# P2_CCD_CAM_BOARD_POWER.net
KiCad netlist of a schematic drawn in Altium Designer
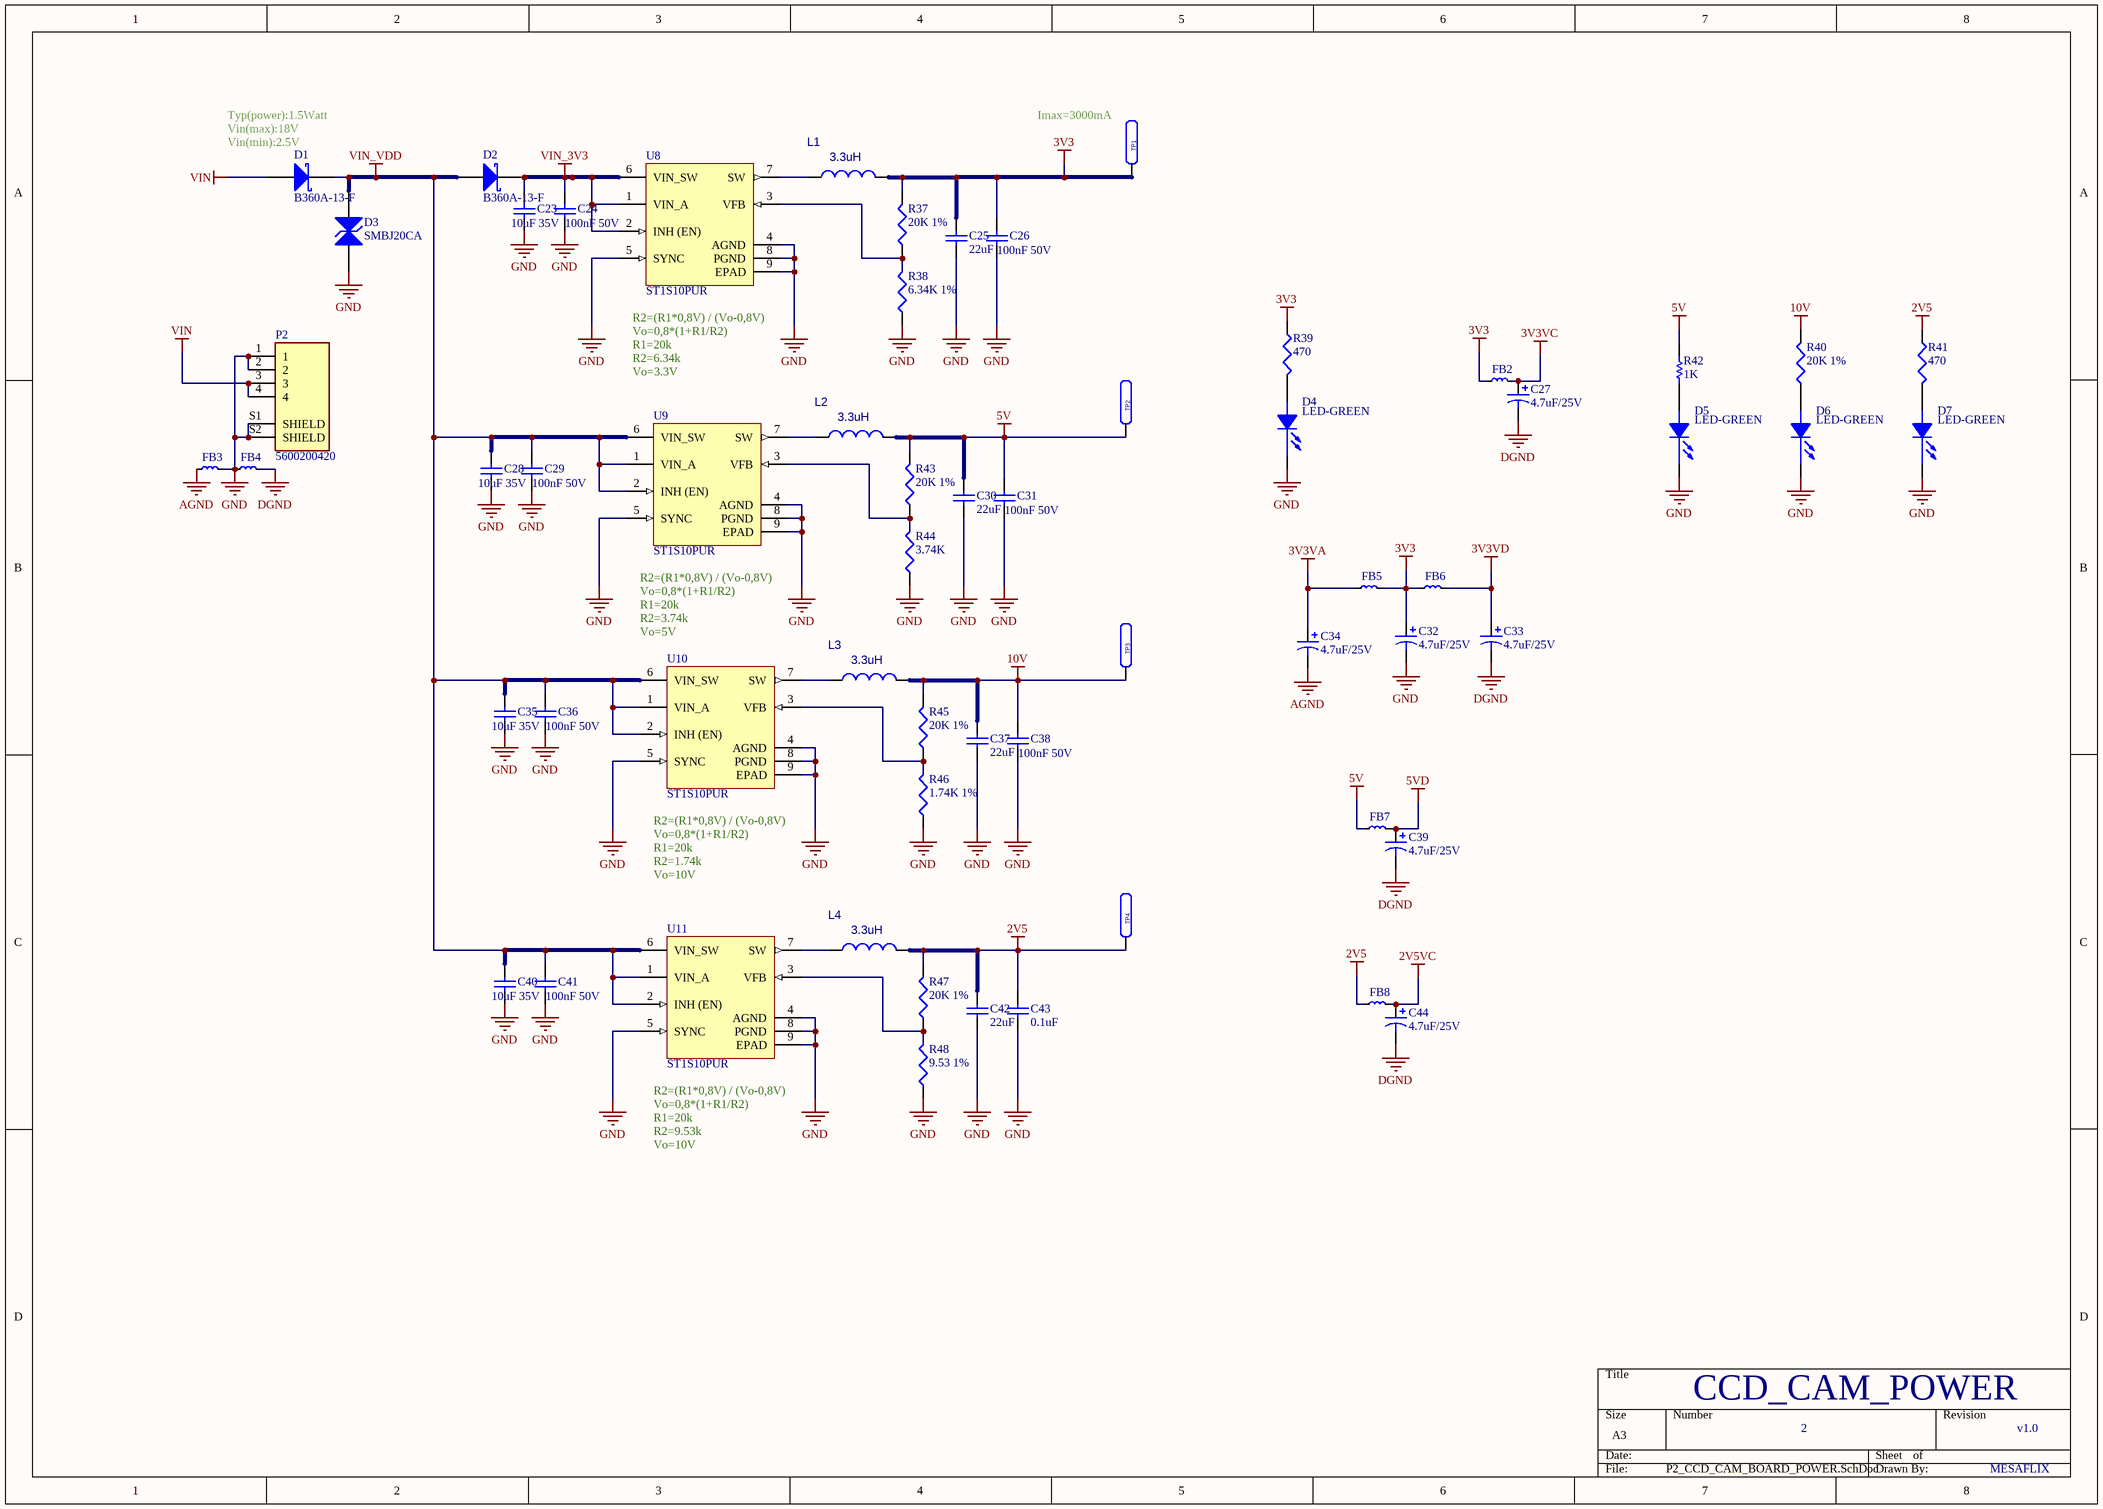
[diagram p0: P2_CCD_CAM_BOARD_POWER.SchDoc]

(export (version "E")
  (design (tool "Eeschema 10.0.6"))
  (components
    (comp (ref "C23")
      (value "10uF 35V")
      (footprint "C 0603(1608)x0.8")
      (description "Cap Ceramic 10uF 35V X5R 20% Pad SMD 0603 85C T/R")
      (fields
        (field (name "MANUFACTURER") "Murata")
        (field (name "MANUFACTURER PART NUMBER") "GRM188R6YA106MA73D")
      )
      (libsource (lib "Miscellaneous Devices") (part "Cap"))
    )
    (comp (ref "C24")
      (value "100nF 50V")
      (footprint "CAP0603")
      (description "CAP CER 0.1UF 50V X7R 0603")
      (libsource (lib "CAP_Library") (part "CAP0603_100nF"))
    )
    (comp (ref "C25")
      (value "22uF")
      (footprint "C 0603(1608)x0.8")
      (description "MURATA - GRM188R60J226MEA0D - CAP, 22µF, 6.3V, 20%, X5R, 0603")
      (fields
        (field (name "MANUFACTURER") "Murata")
        (field (name "MANUFACTURER PART NUMBER") "GRM188R60J226MEA0D")
      )
      (libsource (lib "Miscellaneous Devices") (part "Cap"))
    )
    (comp (ref "C26")
      (value "100nF 50V")
      (footprint "CAP0603")
      (description "CAP CER 0.1UF 50V X7R 0603")
      (libsource (lib "CAP_Library") (part "CAP0603_100nF"))
    )
    (comp (ref "C27")
      (value "4.7uF/25V")
      (footprint "0805 (2012)")
      (fields (field (name "MFR PART #") "GRM219R61E475KA73D"))
      (libsource (lib "CCD_board") (part "Cap Chip Pol"))
    )
    (comp (ref "C28")
      (value "10uF 35V")
      (footprint "C 0603(1608)x0.8")
      (description "Cap Ceramic 10uF 35V X5R 20% Pad SMD 0603 85C T/R")
      (fields
        (field (name "MANUFACTURER") "Murata")
        (field (name "MANUFACTURER PART NUMBER") "GRM188R6YA106MA73D")
      )
      (libsource (lib "Miscellaneous Devices") (part "Cap"))
    )
    (comp (ref "C29")
      (value "100nF 50V")
      (footprint "CAP0603")
      (description "CAP CER 0.1UF 50V X7R 0603")
      (libsource (lib "CAP_Library") (part "CAP0603_100nF"))
    )
    (comp (ref "C30")
      (value "22uF")
      (footprint "C 0603(1608)x0.8")
      (description "MURATA - GRM188R60J226MEA0D - CAP, 22µF, 6.3V, 20%, X5R, 0603")
      (fields
        (field (name "MANUFACTURER") "Murata")
        (field (name "MANUFACTURER PART NUMBER") "GRM188R60J226MEA0D")
      )
      (libsource (lib "Miscellaneous Devices") (part "Cap"))
    )
    (comp (ref "C31")
      (value "100nF 50V")
      (footprint "CAP0603")
      (description "CAP CER 0.1UF 50V X7R 0603")
      (libsource (lib "CAP_Library") (part "CAP0603_100nF"))
    )
    (comp (ref "C32")
      (value "4.7uF/25V")
      (footprint "0805 (2012)")
      (fields (field (name "MFR PART #") "GRM219R61E475KA73D"))
      (libsource (lib "CCD_board") (part "Cap Chip Pol"))
    )
    (comp (ref "C33")
      (value "4.7uF/25V")
      (footprint "0805 (2012)")
      (fields (field (name "MFR PART #") "GRM219R61E475KA73D"))
      (libsource (lib "CCD_board") (part "Cap Chip Pol"))
    )
    (comp (ref "C34")
      (value "4.7uF/25V")
      (footprint "0805 (2012)")
      (fields (field (name "MFR PART #") "GRM219R61E475KA73D"))
      (libsource (lib "CCD_board") (part "Cap Chip Pol"))
    )
    (comp (ref "C35")
      (value "10uF 35V")
      (footprint "C 0603(1608)x0.8")
      (description "Cap Ceramic 10uF 35V X5R 20% Pad SMD 0603 85C T/R")
      (fields
        (field (name "MANUFACTURER") "Murata")
        (field (name "MANUFACTURER PART NUMBER") "GRM188R6YA106MA73D")
      )
      (libsource (lib "Miscellaneous Devices") (part "Cap"))
    )
    (comp (ref "C36")
      (value "100nF 50V")
      (footprint "CAP0603")
      (description "CAP CER 0.1UF 50V X7R 0603")
      (libsource (lib "CAP_Library") (part "CAP0603_100nF"))
    )
    (comp (ref "C37")
      (value "22uF")
      (footprint "C 0603(1608)x0.8")
      (description "MURATA - GRM188R60J226MEA0D - CAP, 22µF, 6.3V, 20%, X5R, 0603")
      (fields
        (field (name "MANUFACTURER") "Murata")
        (field (name "MANUFACTURER PART NUMBER") "GRM188R60J226MEA0D")
      )
      (libsource (lib "Miscellaneous Devices") (part "Cap"))
    )
    (comp (ref "C38")
      (value "100nF 50V")
      (footprint "CAP0603")
      (description "CAP CER 0.1UF 50V X7R 0603")
      (libsource (lib "CAP_Library") (part "CAP0603_100nF"))
    )
    (comp (ref "C39")
      (value "4.7uF/25V")
      (footprint "0805 (2012)")
      (fields (field (name "MFR PART #") "GRM219R61E475KA73D"))
      (libsource (lib "CCD_board") (part "Cap Chip Pol"))
    )
    (comp (ref "C40")
      (value "10uF 35V")
      (footprint "C 0603(1608)x0.8")
      (description "Cap Ceramic 10uF 35V X5R 20% Pad SMD 0603 85C T/R")
      (fields
        (field (name "MANUFACTURER") "Murata")
        (field (name "MANUFACTURER PART NUMBER") "GRM188R6YA106MA73D")
      )
      (libsource (lib "Miscellaneous Devices") (part "Cap"))
    )
    (comp (ref "C41")
      (value "100nF 50V")
      (footprint "CAP0603")
      (description "CAP CER 0.1UF 50V X7R 0603")
      (libsource (lib "CAP_Library") (part "CAP0603_100nF"))
    )
    (comp (ref "C42")
      (value "22uF")
      (footprint "C 0603(1608)x0.8")
      (description "MURATA - GRM188R60J226MEA0D - CAP, 22µF, 6.3V, 20%, X5R, 0603")
      (fields
        (field (name "MANUFACTURER") "Murata")
        (field (name "MANUFACTURER PART NUMBER") "GRM188R60J226MEA0D")
      )
      (libsource (lib "Miscellaneous Devices") (part "Cap"))
    )
    (comp (ref "C43")
      (value "0.1uF")
      (footprint "C 0402(1005)x0.5")
      (description "Capacitor")
      (fields
        (field (name "MANUFACTURER") "Murata")
        (field (name "MANUFACTURER PART NUMBER") "GRM155R71C104KA88D")
      )
      (libsource (lib "Miscellaneous Devices") (part "Cap"))
    )
    (comp (ref "C44")
      (value "4.7uF/25V")
      (footprint "0805 (2012)")
      (fields (field (name "MFR PART #") "GRM219R61E475KA73D"))
      (libsource (lib "CCD_board") (part "Cap Chip Pol"))
    )
    (comp (ref "D1")
      (value "B360A-13-F")
      (footprint "DIOD-B360A_V")
      (description "Schottky Barrier Rectifier, 3 A, -55 to 150 degC, 2-Pin Molded, RoHS, Tape and Reel")
      (fields (field (name "MANUFACTURER") "Diodes"))
      (libsource (lib "KizilTilki_IPEX_Board_V1.0") (part "CMP-2000-05898-1"))
    )
    (comp (ref "D2")
      (value "B360A-13-F")
      (footprint "DIOD-B360A_V")
      (description "Schottky Barrier Rectifier, 3 A, -55 to 150 degC, 2-Pin Molded, RoHS, Tape and Reel")
      (fields (field (name "MANUFACTURER") "Diodes"))
      (libsource (lib "KizilTilki_IPEX_Board_V1.0") (part "CMP-2000-05898-1"))
    )
    (comp (ref "D3")
      (value "SMBJ20CA")
      (footprint "FAIR-DO-214AA-A-2_V")
      (fields (field (name "MANUFACTURER") "Bourns"))
      (libsource (lib "KizilTilki_IPEX_Board_V1.0") (part "CMP-2000-07097-1"))
    )
    (comp (ref "D4")
      (value "LED-GREEN")
      (footprint "LED_0603")
      (description "ROHM         SML-D12P8WT86             LED, EXCELED, Green, SMD, 20 mA, 2.2 V, 560 nm")
      (fields (field (name "MANUFACTURER") "Rohm") (field (name "MANUFACTURER PART NUMBER") "SML-D12P8WT86"))
      (libsource (lib "*") (part "LED"))
    )
    (comp (ref "D5")
      (value "LED-GREEN")
      (footprint "LED_0603")
      (description "ROHM         SML-D12P8WT86             LED, EXCELED, Green, SMD, 20 mA, 2.2 V, 560 nm")
      (fields (field (name "MANUFACTURER") "Rohm") (field (name "MANUFACTURER PART NUMBER") "SML-D12P8WT86"))
      (libsource (lib "*") (part "LED"))
    )
    (comp (ref "D6")
      (value "LED-GREEN")
      (footprint "LED_0603")
      (description "ROHM         SML-D12P8WT86             LED, EXCELED, Green, SMD, 20 mA, 2.2 V, 560 nm")
      (fields (field (name "MANUFACTURER") "Rohm") (field (name "MANUFACTURER PART NUMBER") "SML-D12P8WT86"))
      (libsource (lib "*") (part "LED"))
    )
    (comp (ref "D7")
      (value "LED-GREEN")
      (footprint "LED_0603")
      (description "ROHM         SML-D12P8WT86             LED, EXCELED, Green, SMD, 20 mA, 2.2 V, 560 nm")
      (fields (field (name "MANUFACTURER") "Rohm") (field (name "MANUFACTURER PART NUMBER") "SML-D12P8WT86"))
      (libsource (lib "*") (part "LED"))
    )
    (comp (ref "FB2")
      (value "NFZ2MSD600SN10L")
      (footprint "FB0806")
      (libsource (lib "CCD_board") (part "FB"))
    )
    (comp (ref "FB3")
      (value "NFZ2MSD600SN10L")
      (footprint "FB0806")
      (libsource (lib "CCD_board") (part "FB"))
    )
    (comp (ref "FB4")
      (value "NFZ2MSD600SN10L")
      (footprint "FB0806")
      (libsource (lib "CCD_board") (part "FB"))
    )
    (comp (ref "FB5")
      (value "NFZ2MSD600SN10L")
      (footprint "FB0806")
      (libsource (lib "CCD_board") (part "FB"))
    )
    (comp (ref "FB6")
      (value "NFZ2MSD600SN10L")
      (footprint "FB0806")
      (libsource (lib "CCD_board") (part "FB"))
    )
    (comp (ref "FB7")
      (value "NFZ2MSD600SN10L")
      (footprint "FB0806")
      (libsource (lib "CCD_board") (part "FB"))
    )
    (comp (ref "FB8")
      (value "NFZ2MSD600SN10L")
      (footprint "FB0806")
      (libsource (lib "CCD_board") (part "FB"))
    )
    (comp (ref "L1")
      (value "3.3uH")
      (footprint "IFSC1515AHER")
      (fields
        (field (name "MANUFACTURER") "Vishay Dale")
        (field (name "MANUFACTURER PART NUMBER") "IFSC1515AHER3R3M01")
        (field (name "TOLERANCE") "20%")
      )
      (libsource (lib "*") (part "INDUCTOR"))
    )
    (comp (ref "L2")
      (value "3.3uH")
      (footprint "IFSC1515AHER")
      (fields
        (field (name "MANUFACTURER") "Vishay Dale")
        (field (name "MANUFACTURER PART NUMBER") "IFSC1515AHER3R3M01")
        (field (name "TOLERANCE") "20%")
      )
      (libsource (lib "*") (part "INDUCTOR"))
    )
    (comp (ref "L3")
      (value "3.3uH")
      (footprint "IFSC1515AHER")
      (fields
        (field (name "MANUFACTURER") "Vishay Dale")
        (field (name "MANUFACTURER PART NUMBER") "IFSC1515AHER3R3M01")
        (field (name "TOLERANCE") "20%")
      )
      (libsource (lib "*") (part "INDUCTOR"))
    )
    (comp (ref "L4")
      (value "3.3uH")
      (footprint "IFSC1515AHER")
      (fields
        (field (name "MANUFACTURER") "Vishay Dale")
        (field (name "MANUFACTURER PART NUMBER") "IFSC1515AHER3R3M01")
        (field (name "TOLERANCE") "20%")
      )
      (libsource (lib "*") (part "INDUCTOR"))
    )
    (comp (ref "P2")
      (value "5600200420")
      (footprint "MOLEX_5600200420_3D")
      (description "Connector Header Surface Mount 4 position 0.079 (2.00mm)")
      (fields (field (name "MF") "Molex"))
      (libsource (lib "CCD_CAM_BOARD_3") (part "5600200420"))
    )
    (comp (ref "R37")
      (value "20K 1%")
      (footprint "R 0402(1005)")
      (description "RES 20K OHM 1% 1/16W 0402")
      (fields
        (field (name "MANUFACTURER") "Vishay")
        (field (name "MANUFACTURER PART NUMBER") "CRCW040220K0FKEDC")
      )
      (libsource (lib "Miscellaneous Devices") (part "Res3"))
    )
    (comp (ref "R38")
      (value "6.34K 1%")
      (footprint "R 0402(1005)")
      (description "RES SMD 6.34K OHM 1% 1/16W 0402")
      (libsource (lib "Miscellaneous Devices") (part "Res3"))
    )
    (comp (ref "R39")
      (value "470")
      (footprint "R 0402(1005)")
      (description "RES SMD 470 OHM 5% 1/16W 0402")
      (fields
        (field (name "MANUFACTURER") "Yageo")
        (field (name "MANUFACTURER PART NUMBER") "RC0402JR-07470RL")
      )
      (libsource (lib "Miscellaneous Devices") (part "Res3"))
    )
    (comp (ref "R40")
      (value "20K 1%")
      (footprint "R 0402(1005)")
      (description "RES 20K OHM 1% 1/16W 0402")
      (fields
        (field (name "MANUFACTURER") "Vishay")
        (field (name "MANUFACTURER PART NUMBER") "CRCW040220K0FKEDC")
      )
      (libsource (lib "Miscellaneous Devices") (part "Res3"))
    )
    (comp (ref "R41")
      (value "470")
      (footprint "R 0402(1005)")
      (description "RES SMD 470 OHM 5% 1/16W 0402")
      (fields
        (field (name "MANUFACTURER") "Yageo")
        (field (name "MANUFACTURER PART NUMBER") "RC0402JR-07470RL")
      )
      (libsource (lib "Miscellaneous Devices") (part "Res3"))
    )
    (comp (ref "R42")
      (value "1K")
      (footprint "CAP_RES_1608_0603")
      (fields
        (field (name "DIGIKEYPARTNUMBER") "YAG3646CT-ND")
        (field (name "MANUFACTURER") "Yageo")
        (field (name "MANUFACTURERPARTNUMBER") "AC0603JR-071KL")
      )
      (libsource (lib "TESLA_PCB_LIB") (part "RES_1K_0603"))
    )
    (comp (ref "R43")
      (value "20K 1%")
      (footprint "R 0402(1005)")
      (description "RES 20K OHM 1% 1/16W 0402")
      (fields
        (field (name "MANUFACTURER") "Vishay")
        (field (name "MANUFACTURER PART NUMBER") "CRCW040220K0FKEDC")
      )
      (libsource (lib "Miscellaneous Devices") (part "Res3"))
    )
    (comp (ref "R44")
      (value "3.74K")
      (footprint "R 0402(1005)")
      (description "RES SMD 5.49K OHM 1% 1/16W 0402")
      (fields (field (name "MPN") "RC0402FR-073K74L"))
      (libsource (lib "Miscellaneous Devices") (part "Res3"))
    )
    (comp (ref "R45")
      (value "20K 1%")
      (footprint "R 0402(1005)")
      (description "RES 20K OHM 1% 1/16W 0402")
      (fields
        (field (name "MANUFACTURER") "Vishay")
        (field (name "MANUFACTURER PART NUMBER") "CRCW040220K0FKEDC")
      )
      (libsource (lib "Miscellaneous Devices") (part "Res3"))
    )
    (comp (ref "R46")
      (value "1.74K 1%")
      (footprint "R 0402(1005)")
      (description "RES SMD 1.74K OHM 1% 1/16W 0402")
      (fields (field (name "MPN") "RC0402FR-071K74L"))
      (libsource (lib "Miscellaneous Devices") (part "Res3"))
    )
    (comp (ref "R47")
      (value "20K 1%")
      (footprint "R 0402(1005)")
      (description "RES 20K OHM 1% 1/16W 0402")
      (fields
        (field (name "MANUFACTURER") "Vishay")
        (field (name "MANUFACTURER PART NUMBER") "CRCW040220K0FKEDC")
      )
      (libsource (lib "Miscellaneous Devices") (part "Res3"))
    )
    (comp (ref "R48")
      (value "9.53 1%")
      (footprint "R 0402(1005)")
      (description "RES SMD 5.53K OHM 1% 1/16W 0402")
      (fields (field (name "MPN") "RC0603FR-079K53L"))
      (libsource (lib "Miscellaneous Devices") (part "Res3"))
    )
    (comp (ref "TP1")
      (value "3V7")
      (footprint "LTPT35C49P")
      (libsource (lib "CAMERA_MODULE_JETSON_SONY") (part "LABTESTPOINT"))
    )
    (comp (ref "TP2")
      (value "3V7")
      (footprint "LTPT35C49P")
      (libsource (lib "CAMERA_MODULE_JETSON_SONY") (part "LABTESTPOINT"))
    )
    (comp (ref "TP3")
      (value "3V7")
      (footprint "LTPT35C49P")
      (libsource (lib "CAMERA_MODULE_JETSON_SONY") (part "LABTESTPOINT"))
    )
    (comp (ref "TP4")
      (value "3V7")
      (footprint "LTPT35C49P")
      (libsource (lib "CAMERA_MODULE_JETSON_SONY") (part "LABTESTPOINT"))
    )
    (comp (ref "U8")
      (value "ST1S10PUR")
      (footprint "DFN(4x4)_N")
      (description "Monolithic synchronous step-down regulator, 8-Pin DFN, Tape and Reel")
      (fields (field (name "MANUFACTURER") "STMicroelectronics"))
      (libsource (lib "KizilTilki_IPEX_Board_V1.0") (part "CMP-0240-00156-1"))
    )
    (comp (ref "U9")
      (value "ST1S10PUR")
      (footprint "DFN(4x4)_N")
      (description "Monolithic synchronous step-down regulator, 8-Pin DFN, Tape and Reel")
      (fields (field (name "MANUFACTURER") "STMicroelectronics"))
      (libsource (lib "KizilTilki_IPEX_Board_V1.0") (part "CMP-0240-00156-1"))
    )
    (comp (ref "U10")
      (value "ST1S10PUR")
      (footprint "DFN(4x4)_N")
      (description "Monolithic synchronous step-down regulator, 8-Pin DFN, Tape and Reel")
      (fields (field (name "MANUFACTURER") "STMicroelectronics"))
      (libsource (lib "KizilTilki_IPEX_Board_V1.0") (part "CMP-0240-00156-1"))
    )
    (comp (ref "U11")
      (value "ST1S10PUR")
      (footprint "DFN(4x4)_N")
      (description "Monolithic synchronous step-down regulator, 8-Pin DFN, Tape and Reel")
      (fields (field (name "MANUFACTURER") "STMicroelectronics"))
      (libsource (lib "KizilTilki_IPEX_Board_V1.0") (part "CMP-0240-00156-1"))
    )
  )
  (nets
    (net (code "1") (name "2V5") (class "Default")
      (node (ref "C42") (pin "1") (pinfunction "1_1") (pintype "passive"))
      (node (ref "C43") (pin "2") (pinfunction "2_2") (pintype "passive"))
      (node (ref "FB8") (pin "1") (pintype "passive"))
      (node (ref "L4") (pin "2") (pinfunction "2_2") (pintype "passive"))
      (node (ref "R41") (pin "1") (pinfunction "1_1") (pintype "passive"))
      (node (ref "R47") (pin "2") (pinfunction "2_2") (pintype "passive"))
      (node (ref "TP4") (pin "1") (pinfunction "1_1") (pintype "passive"))
    )
    (net (code "2") (name "2V5VC") (class "Default")
      (node (ref "C44") (pin "1") (pinfunction "1_1") (pintype "passive"))
      (node (ref "FB8") (pin "2") (pintype "passive"))
    )
    (net (code "3") (name "3V3") (class "Default")
      (node (ref "C25") (pin "1") (pinfunction "1_1") (pintype "passive"))
      (node (ref "C26") (pin "2") (pinfunction "2_2") (pintype "passive"))
      (node (ref "C32") (pin "1") (pinfunction "1_1") (pintype "passive"))
      (node (ref "FB2") (pin "1") (pintype "passive"))
      (node (ref "FB5") (pin "2") (pintype "passive"))
      (node (ref "FB6") (pin "1") (pintype "passive"))
      (node (ref "L1") (pin "2") (pinfunction "2_2") (pintype "passive"))
      (node (ref "R37") (pin "2") (pinfunction "2_2") (pintype "passive"))
      (node (ref "R39") (pin "1") (pinfunction "1_1") (pintype "passive"))
      (node (ref "TP1") (pin "1") (pinfunction "1_1") (pintype "passive"))
    )
    (net (code "4") (name "3V3VA") (class "Default")
      (node (ref "C34") (pin "1") (pinfunction "1_1") (pintype "passive"))
      (node (ref "FB5") (pin "1") (pintype "passive"))
    )
    (net (code "5") (name "3V3VC") (class "Default")
      (node (ref "C27") (pin "1") (pinfunction "1_1") (pintype "passive"))
      (node (ref "FB2") (pin "2") (pintype "passive"))
    )
    (net (code "6") (name "3V3VD") (class "Default")
      (node (ref "C33") (pin "1") (pinfunction "1_1") (pintype "passive"))
      (node (ref "FB6") (pin "2") (pintype "passive"))
    )
    (net (code "7") (name "5V") (class "Default")
      (node (ref "C30") (pin "1") (pinfunction "1_1") (pintype "passive"))
      (node (ref "C31") (pin "2") (pinfunction "2_2") (pintype "passive"))
      (node (ref "FB7") (pin "1") (pintype "passive"))
      (node (ref "L2") (pin "2") (pinfunction "2_2") (pintype "passive"))
      (node (ref "R42") (pin "1") (pinfunction "1_1") (pintype "passive"))
      (node (ref "R43") (pin "2") (pinfunction "2_2") (pintype "passive"))
      (node (ref "TP2") (pin "1") (pinfunction "1_1") (pintype "passive"))
    )
    (net (code "8") (name "5VD") (class "Default")
      (node (ref "C39") (pin "1") (pinfunction "1_1") (pintype "passive"))
      (node (ref "FB7") (pin "2") (pintype "passive"))
    )
    (net (code "9") (name "10V") (class "Default")
      (node (ref "C37") (pin "1") (pinfunction "1_1") (pintype "passive"))
      (node (ref "C38") (pin "2") (pinfunction "2_2") (pintype "passive"))
      (node (ref "L3") (pin "2") (pinfunction "2_2") (pintype "passive"))
      (node (ref "R40") (pin "2") (pinfunction "2_2") (pintype "passive"))
      (node (ref "R45") (pin "2") (pinfunction "2_2") (pintype "passive"))
      (node (ref "TP3") (pin "1") (pinfunction "1_1") (pintype "passive"))
    )
    (net (code "10") (name "AGND") (class "Default")
      (node (ref "C34") (pin "2") (pinfunction "2_2") (pintype "passive"))
      (node (ref "FB3") (pin "1") (pintype "passive"))
    )
    (net (code "11") (name "DGND") (class "Default")
      (node (ref "C27") (pin "2") (pinfunction "2_2") (pintype "passive"))
      (node (ref "C33") (pin "2") (pinfunction "2_2") (pintype "passive"))
      (node (ref "C39") (pin "2") (pinfunction "2_2") (pintype "passive"))
      (node (ref "C44") (pin "2") (pinfunction "2_2") (pintype "passive"))
      (node (ref "FB4") (pin "2") (pintype "passive"))
    )
    (net (code "12") (name "GND") (class "Default")
      (node (ref "C23") (pin "2") (pinfunction "2_2") (pintype "passive"))
      (node (ref "C24") (pin "1") (pinfunction "1_1") (pintype "passive"))
      (node (ref "C25") (pin "2") (pinfunction "2_2") (pintype "passive"))
      (node (ref "C26") (pin "1") (pinfunction "1_1") (pintype "passive"))
      (node (ref "C28") (pin "2") (pinfunction "2_2") (pintype "passive"))
      (node (ref "C29") (pin "1") (pinfunction "1_1") (pintype "passive"))
      (node (ref "C30") (pin "2") (pinfunction "2_2") (pintype "passive"))
      (node (ref "C31") (pin "1") (pinfunction "1_1") (pintype "passive"))
      (node (ref "C32") (pin "2") (pinfunction "2_2") (pintype "passive"))
      (node (ref "C35") (pin "2") (pinfunction "2_2") (pintype "passive"))
      (node (ref "C36") (pin "1") (pinfunction "1_1") (pintype "passive"))
      (node (ref "C37") (pin "2") (pinfunction "2_2") (pintype "passive"))
      (node (ref "C38") (pin "1") (pinfunction "1_1") (pintype "passive"))
      (node (ref "C40") (pin "2") (pinfunction "2_2") (pintype "passive"))
      (node (ref "C41") (pin "1") (pinfunction "1_1") (pintype "passive"))
      (node (ref "C42") (pin "2") (pinfunction "2_2") (pintype "passive"))
      (node (ref "C43") (pin "1") (pinfunction "1_1") (pintype "passive"))
      (node (ref "D3") (pin "1") (pinfunction "A_1") (pintype "passive"))
      (node (ref "D4") (pin "2") (pinfunction "CATHODE_2") (pintype "passive"))
      (node (ref "D5") (pin "2") (pinfunction "CATHODE_2") (pintype "passive"))
      (node (ref "D6") (pin "2") (pinfunction "CATHODE_2") (pintype "passive"))
      (node (ref "D7") (pin "2") (pinfunction "CATHODE_2") (pintype "passive"))
      (node (ref "FB3") (pin "2") (pintype "passive"))
      (node (ref "FB4") (pin "1") (pintype "passive"))
      (node (ref "P2") (pin "1") (pinfunction "1_1") (pintype "passive"))
      (node (ref "P2") (pin "2") (pinfunction "2_2") (pintype "passive"))
      (node (ref "P2") (pin "S1") (pinfunction "SHIELD_S1") (pintype "passive"))
      (node (ref "P2") (pin "S2") (pinfunction "SHIELD_S2") (pintype "passive"))
      (node (ref "R38") (pin "1") (pinfunction "1_1") (pintype "passive"))
      (node (ref "R44") (pin "1") (pinfunction "1_1") (pintype "passive"))
      (node (ref "R46") (pin "1") (pinfunction "1_1") (pintype "passive"))
      (node (ref "R48") (pin "1") (pinfunction "1_1") (pintype "passive"))
      (node (ref "U10") (pin "4") (pinfunction "AGND_4") (pintype "power_in"))
      (node (ref "U10") (pin "5") (pinfunction "SYNC_5") (pintype "input"))
      (node (ref "U10") (pin "8") (pinfunction "PGND_8") (pintype "power_in"))
      (node (ref "U10") (pin "9") (pinfunction "EPAD_9") (pintype "power_in"))
      (node (ref "U11") (pin "4") (pinfunction "AGND_4") (pintype "power_in"))
      (node (ref "U11") (pin "5") (pinfunction "SYNC_5") (pintype "input"))
      (node (ref "U11") (pin "8") (pinfunction "PGND_8") (pintype "power_in"))
      (node (ref "U11") (pin "9") (pinfunction "EPAD_9") (pintype "power_in"))
      (node (ref "U8") (pin "4") (pinfunction "AGND_4") (pintype "power_in"))
      (node (ref "U8") (pin "5") (pinfunction "SYNC_5") (pintype "input"))
      (node (ref "U8") (pin "8") (pinfunction "PGND_8") (pintype "power_in"))
      (node (ref "U8") (pin "9") (pinfunction "EPAD_9") (pintype "power_in"))
      (node (ref "U9") (pin "4") (pinfunction "AGND_4") (pintype "power_in"))
      (node (ref "U9") (pin "5") (pinfunction "SYNC_5") (pintype "input"))
      (node (ref "U9") (pin "8") (pinfunction "PGND_8") (pintype "power_in"))
      (node (ref "U9") (pin "9") (pinfunction "EPAD_9") (pintype "power_in"))
    )
    (net (code "13") (name "Net-(D4-ANODE)") (class "Default")
      (node (ref "D4") (pin "1") (pinfunction "ANODE_1") (pintype "passive"))
      (node (ref "R39") (pin "2") (pinfunction "2_2") (pintype "passive"))
    )
    (net (code "14") (name "Net-(D5-ANODE)") (class "Default")
      (node (ref "D5") (pin "1") (pinfunction "ANODE_1") (pintype "passive"))
      (node (ref "R42") (pin "2") (pinfunction "2_2") (pintype "passive"))
    )
    (net (code "15") (name "Net-(D6-ANODE)") (class "Default")
      (node (ref "D6") (pin "1") (pinfunction "ANODE_1") (pintype "passive"))
      (node (ref "R40") (pin "1") (pinfunction "1_1") (pintype "passive"))
    )
    (net (code "16") (name "Net-(D7-ANODE)") (class "Default")
      (node (ref "D7") (pin "1") (pinfunction "ANODE_1") (pintype "passive"))
      (node (ref "R41") (pin "2") (pinfunction "2_2") (pintype "passive"))
    )
    (net (code "17") (name "Net-(U8-SW)") (class "Default")
      (node (ref "L1") (pin "1") (pinfunction "1_1") (pintype "passive"))
      (node (ref "U8") (pin "7") (pinfunction "SW_7") (pintype "output"))
    )
    (net (code "18") (name "Net-(U8-VFB)") (class "Default")
      (node (ref "R37") (pin "1") (pinfunction "1_1") (pintype "passive"))
      (node (ref "R38") (pin "2") (pinfunction "2_2") (pintype "passive"))
      (node (ref "U8") (pin "3") (pinfunction "VFB_3") (pintype "input"))
    )
    (net (code "19") (name "Net-(U9-SW)") (class "Default")
      (node (ref "L2") (pin "1") (pinfunction "1_1") (pintype "passive"))
      (node (ref "U9") (pin "7") (pinfunction "SW_7") (pintype "output"))
    )
    (net (code "20") (name "Net-(U9-VFB)") (class "Default")
      (node (ref "R43") (pin "1") (pinfunction "1_1") (pintype "passive"))
      (node (ref "R44") (pin "2") (pinfunction "2_2") (pintype "passive"))
      (node (ref "U9") (pin "3") (pinfunction "VFB_3") (pintype "input"))
    )
    (net (code "21") (name "Net-(U10-SW)") (class "Default")
      (node (ref "L3") (pin "1") (pinfunction "1_1") (pintype "passive"))
      (node (ref "U10") (pin "7") (pinfunction "SW_7") (pintype "output"))
    )
    (net (code "22") (name "Net-(U10-VFB)") (class "Default")
      (node (ref "R45") (pin "1") (pinfunction "1_1") (pintype "passive"))
      (node (ref "R46") (pin "2") (pinfunction "2_2") (pintype "passive"))
      (node (ref "U10") (pin "3") (pinfunction "VFB_3") (pintype "input"))
    )
    (net (code "23") (name "Net-(U11-SW)") (class "Default")
      (node (ref "L4") (pin "1") (pinfunction "1_1") (pintype "passive"))
      (node (ref "U11") (pin "7") (pinfunction "SW_7") (pintype "output"))
    )
    (net (code "24") (name "Net-(U11-VFB)") (class "Default")
      (node (ref "R47") (pin "1") (pinfunction "1_1") (pintype "passive"))
      (node (ref "R48") (pin "2") (pinfunction "2_2") (pintype "passive"))
      (node (ref "U11") (pin "3") (pinfunction "VFB_3") (pintype "input"))
    )
    (net (code "25") (name "VIN") (class "Default")
      (node (ref "D1") (pin "1") (pinfunction "A_1") (pintype "passive"))
      (node (ref "P2") (pin "3") (pinfunction "3_3") (pintype "passive"))
      (node (ref "P2") (pin "4") (pinfunction "4_4") (pintype "passive"))
    )
    (net (code "26") (name "VIN_3V3") (class "Default")
      (node (ref "C23") (pin "1") (pinfunction "1_1") (pintype "passive"))
      (node (ref "C24") (pin "2") (pinfunction "2_2") (pintype "passive"))
      (node (ref "D2") (pin "2") (pinfunction "K_2") (pintype "passive"))
      (node (ref "U8") (pin "1") (pinfunction "VIN_A_1") (pintype "power_in"))
      (node (ref "U8") (pin "2") (pinfunction "INH_(EN)_2") (pintype "input"))
      (node (ref "U8") (pin "6") (pinfunction "VIN_SW_6") (pintype "power_in"))
    )
    (net (code "27") (name "VIN_VDD") (class "Default")
      (node (ref "C28") (pin "1") (pinfunction "1_1") (pintype "passive"))
      (node (ref "C29") (pin "2") (pinfunction "2_2") (pintype "passive"))
      (node (ref "C35") (pin "1") (pinfunction "1_1") (pintype "passive"))
      (node (ref "C36") (pin "2") (pinfunction "2_2") (pintype "passive"))
      (node (ref "C40") (pin "1") (pinfunction "1_1") (pintype "passive"))
      (node (ref "C41") (pin "2") (pinfunction "2_2") (pintype "passive"))
      (node (ref "D1") (pin "2") (pinfunction "K_2") (pintype "passive"))
      (node (ref "D2") (pin "1") (pinfunction "A_1") (pintype "passive"))
      (node (ref "D3") (pin "2") (pinfunction "A_2") (pintype "passive"))
      (node (ref "U10") (pin "1") (pinfunction "VIN_A_1") (pintype "power_in"))
      (node (ref "U10") (pin "2") (pinfunction "INH_(EN)_2") (pintype "input"))
      (node (ref "U10") (pin "6") (pinfunction "VIN_SW_6") (pintype "power_in"))
      (node (ref "U11") (pin "1") (pinfunction "VIN_A_1") (pintype "power_in"))
      (node (ref "U11") (pin "2") (pinfunction "INH_(EN)_2") (pintype "input"))
      (node (ref "U11") (pin "6") (pinfunction "VIN_SW_6") (pintype "power_in"))
      (node (ref "U9") (pin "1") (pinfunction "VIN_A_1") (pintype "power_in"))
      (node (ref "U9") (pin "2") (pinfunction "INH_(EN)_2") (pintype "input"))
      (node (ref "U9") (pin "6") (pinfunction "VIN_SW_6") (pintype "power_in"))
    )
  )
)
